# light_switch_smd2.net
KiCad netlist of a schematic drawn in EAGLE
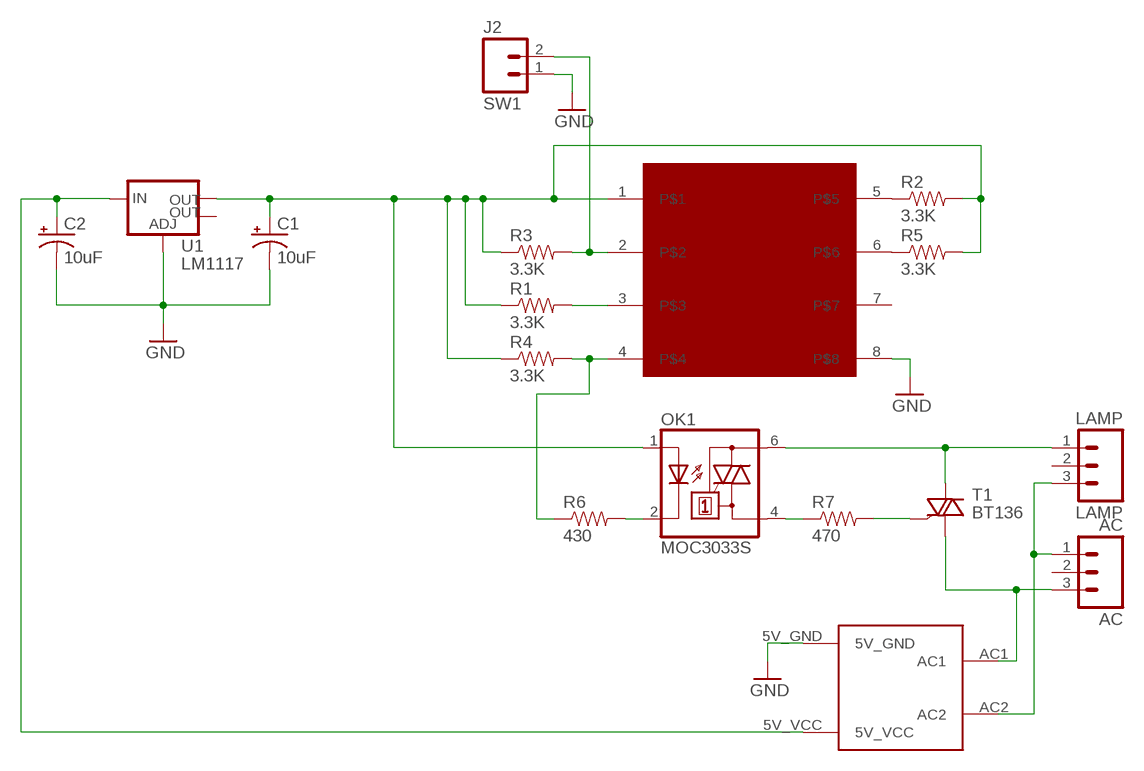
[diagram p0: schematic, sheet 1]

(export (version "E")
  (design (tool "Eeschema 10.0.6"))
  (components
    (comp (ref "AC")
      (value "AC")
      (footprint "eagle-import:1X03_NO_SILK")
      (libsource (lib "eagle-import") (part "M031X03_NO_SILK"))
    )
    (comp (ref "C1")
      (value "10uF")
      (footprint "eagle-import:EIA3216")
      (libsource (lib "eagle-import") (part "10UF-16V-10%(TANT)"))
    )
    (comp (ref "C2")
      (value "10uF")
      (footprint "eagle-import:EIA3216")
      (libsource (lib "eagle-import") (part "10UF-16V-10%(TANT)"))
    )
    (comp (ref "J2")
      (value "SW1")
      (footprint "eagle-import:1X02_LONGPADS")
      (libsource (lib "eagle-import") (part "M02PTH3"))
    )
    (comp (ref "LAMP")
      (value "LAMP")
      (footprint "eagle-import:1X03_NO_SILK")
      (libsource (lib "eagle-import") (part "M031X03_NO_SILK"))
    )
    (comp (ref "OK1")
      (value "MOC3033S")
      (footprint "eagle-import:DIL6-SMD")
      (fields (field (name "MF") "FAIRCHILD SEMICONDUCTOR") (field (name "MPN") "MOC3033S-M"))
      (libsource (lib "eagle-import") (part "MOC30S33"))
    )
    (comp (ref "R1")
      (value "3.3K")
      (footprint "eagle-import:1206")
      (libsource (lib "eagle-import") (part "RESISTOR1206"))
    )
    (comp (ref "R2")
      (value "3.3K")
      (footprint "eagle-import:1206")
      (libsource (lib "eagle-import") (part "RESISTOR1206"))
    )
    (comp (ref "R3")
      (value "3.3K")
      (footprint "eagle-import:1206")
      (libsource (lib "eagle-import") (part "RESISTOR1206"))
    )
    (comp (ref "R4")
      (value "3.3K")
      (footprint "eagle-import:1206")
      (libsource (lib "eagle-import") (part "RESISTOR1206"))
    )
    (comp (ref "R5")
      (value "3.3K")
      (footprint "eagle-import:1206")
      (libsource (lib "eagle-import") (part "RESISTOR1206"))
    )
    (comp (ref "R6")
      (value "430")
      (footprint "eagle-import:1206")
      (libsource (lib "eagle-import") (part "RESISTOR1206"))
    )
    (comp (ref "R7")
      (value "470")
      (footprint "eagle-import:1206")
      (libsource (lib "eagle-import") (part "RESISTOR1206"))
    )
    (comp (ref "T1")
      (value "BT136")
      (footprint "eagle-import:TO220AB")
      (libsource (lib "eagle-import") (part "BT136"))
    )
    (comp (ref "U$1")
      (value "HI-LINK5V-ACDC")
      (footprint "eagle-import:AC5V")
      (libsource (lib "eagle-import") (part "HI-LINK5V-ACDC"))
    )
    (comp (ref "U$2")
      (value "ESP8266-01")
      (footprint "eagle-import:ESP8266-01")
      (libsource (lib "eagle-import") (part "ESP8266-01"))
    )
    (comp (ref "U1")
      (value "LM1117")
      (footprint "eagle-import:SOT223")
      (libsource (lib "eagle-import") (part "V_REG_LM1117SOT223"))
    )
  )
  (nets
    (net (code "1") (name "GND") (class "Default")
      (node (ref "C1") (pin "C") (pinfunction "-_C") (pintype "passive"))
      (node (ref "C2") (pin "C") (pinfunction "-_C") (pintype "passive"))
      (node (ref "J2") (pin "1") (pinfunction "1_1") (pintype "passive"))
      (node (ref "U$1") (pin "5V_GND") (pinfunction "5V_GND_5V_GND") (pintype "bidirectional"))
      (node (ref "U$2") (pin "8") (pinfunction "P$8_8") (pintype "bidirectional"))
      (node (ref "U1") (pin "1") (pinfunction "ADJ_1") (pintype "input"))
    )
    (net (code "2") (name "Net-(AC-Pad1)") (class "Default")
      (node (ref "AC") (pin "1") (pinfunction "1_1") (pintype "passive"))
      (node (ref "LAMP") (pin "3") (pinfunction "3_3") (pintype "passive"))
      (node (ref "U$1") (pin "AC2") (pinfunction "AC2_AC2") (pintype "bidirectional"))
    )
    (net (code "3") (name "Net-(C1-+)") (class "Default")
      (node (ref "C1") (pin "A") (pinfunction "+_A") (pintype "passive"))
      (node (ref "OK1") (pin "1") (pinfunction "A_1") (pintype "passive"))
      (node (ref "R1") (pin "1") (pinfunction "1_1") (pintype "passive"))
      (node (ref "R2") (pin "2") (pinfunction "2_2") (pintype "passive"))
      (node (ref "R3") (pin "1") (pinfunction "1_1") (pintype "passive"))
      (node (ref "R4") (pin "1") (pinfunction "1_1") (pintype "passive"))
      (node (ref "R5") (pin "2") (pinfunction "2_2") (pintype "passive"))
      (node (ref "U$2") (pin "1") (pinfunction "P$1_1") (pintype "bidirectional"))
      (node (ref "U1") (pin "2") (pinfunction "OUT_2") (pintype "output"))
    )
    (net (code "4") (name "Net-(C2-+)") (class "Default")
      (node (ref "C2") (pin "A") (pinfunction "+_A") (pintype "passive"))
      (node (ref "U$1") (pin "5V_VCC") (pinfunction "5V_VCC_5V_VCC") (pintype "bidirectional"))
      (node (ref "U1") (pin "3") (pinfunction "IN_3") (pintype "input"))
    )
    (net (code "5") (name "Net-(OK1-A1)") (class "Default")
      (node (ref "OK1") (pin "4") (pinfunction "A1_4") (pintype "passive"))
      (node (ref "R7") (pin "1") (pinfunction "1_1") (pintype "passive"))
    )
    (net (code "6") (name "Net-(OK1-A2)") (class "Default")
      (node (ref "LAMP") (pin "1") (pinfunction "1_1") (pintype "passive"))
      (node (ref "OK1") (pin "6") (pinfunction "A2_6") (pintype "passive"))
      (node (ref "T1") (pin "2") (pinfunction "A2_2") (pintype "passive"))
    )
    (net (code "7") (name "Net-(OK1-C)") (class "Default")
      (node (ref "OK1") (pin "2") (pinfunction "C_2") (pintype "passive"))
      (node (ref "R6") (pin "2") (pinfunction "2_2") (pintype "passive"))
    )
    (net (code "8") (name "Net-(T1-A1)") (class "Default")
      (node (ref "AC") (pin "3") (pinfunction "3_3") (pintype "passive"))
      (node (ref "T1") (pin "1") (pinfunction "A1_1") (pintype "passive"))
      (node (ref "U$1") (pin "AC1") (pinfunction "AC1_AC1") (pintype "bidirectional"))
    )
    (net (code "9") (name "Net-(T1-G)") (class "Default")
      (node (ref "R7") (pin "2") (pinfunction "2_2") (pintype "passive"))
      (node (ref "T1") (pin "3") (pinfunction "G_3") (pintype "passive"))
    )
    (net (code "10") (name "Net-(U$2-P$2)") (class "Default")
      (node (ref "J2") (pin "2") (pinfunction "2_2") (pintype "passive"))
      (node (ref "R3") (pin "2") (pinfunction "2_2") (pintype "passive"))
      (node (ref "U$2") (pin "2") (pinfunction "P$2_2") (pintype "bidirectional"))
    )
    (net (code "11") (name "Net-(U$2-P$3)") (class "Default")
      (node (ref "R1") (pin "2") (pinfunction "2_2") (pintype "passive"))
      (node (ref "U$2") (pin "3") (pinfunction "P$3_3") (pintype "bidirectional"))
    )
    (net (code "12") (name "Net-(U$2-P$4)") (class "Default")
      (node (ref "R4") (pin "2") (pinfunction "2_2") (pintype "passive"))
      (node (ref "R6") (pin "1") (pinfunction "1_1") (pintype "passive"))
      (node (ref "U$2") (pin "4") (pinfunction "P$4_4") (pintype "bidirectional"))
    )
    (net (code "13") (name "Net-(U$2-P$5)") (class "Default")
      (node (ref "R2") (pin "1") (pinfunction "1_1") (pintype "passive"))
      (node (ref "U$2") (pin "5") (pinfunction "P$5_5") (pintype "bidirectional"))
    )
    (net (code "14") (name "Net-(U$2-P$6)") (class "Default")
      (node (ref "R5") (pin "1") (pinfunction "1_1") (pintype "passive"))
      (node (ref "U$2") (pin "6") (pinfunction "P$6_6") (pintype "bidirectional"))
    )
    (net (code "15") (name "unconnected-(AC-Pad2)") (class "Default")
      (node (ref "AC") (pin "2") (pinfunction "2_2") (pintype "passive"))
    )
    (net (code "16") (name "unconnected-(LAMP-Pad2)") (class "Default")
      (node (ref "LAMP") (pin "2") (pinfunction "2_2") (pintype "passive"))
    )
    (net (code "17") (name "unconnected-(U$2-P$7-Pad7)") (class "Default")
      (node (ref "U$2") (pin "7") (pinfunction "P$7_7") (pintype "bidirectional"))
    )
    (net (code "18") (name "unconnected-(U1-OUT-Pad4)") (class "Default")
      (node (ref "U1") (pin "4") (pinfunction "OUT_4") (pintype "output"))
    )
  )
)
